# NinjaLAMP_Arduino_simple.net
KiCad netlist of a schematic drawn in EAGLE
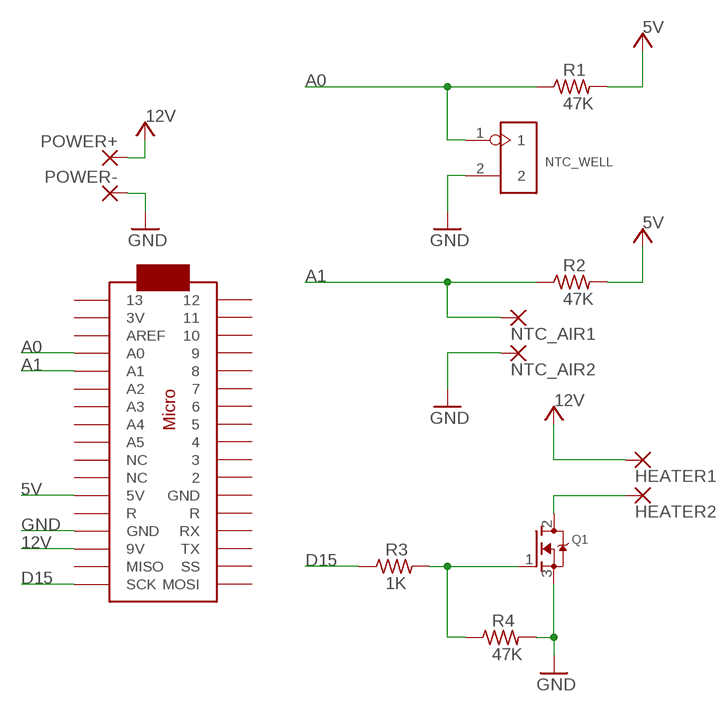
[diagram p0: schematic, sheet 1]

(export (version "E")
  (design (tool "Eeschema 10.0.6"))
  (components
    (comp (ref "HEATER1")
      (value "1,6/0,8")
      (footprint "eagle-import:1,6_0,8")
      (libsource (lib "eagle-import") (part "1,6/0,8"))
    )
    (comp (ref "HEATER2")
      (value "1,6/0,8")
      (footprint "eagle-import:1,6_0,8")
      (libsource (lib "eagle-import") (part "1,6/0,8"))
    )
    (comp (ref "NTC_AIR1")
      (value "1,6/0,8")
      (footprint "eagle-import:1,6_0,8")
      (libsource (lib "eagle-import") (part "1,6/0,8"))
    )
    (comp (ref "NTC_AIR2")
      (value "1,6/0,8")
      (footprint "eagle-import:1,6_0,8")
      (libsource (lib "eagle-import") (part "1,6/0,8"))
    )
    (comp (ref "NTC_WELL")
      (value "2p-2.54")
      (footprint "eagle-import:H2-2.54")
      (fields (field (name "MPN") "P125-1102A0BS116A1"))
      (libsource (lib "eagle-import") (part "DIP-BLACK-MALE-HEADER-VERT(2P-2.54)"))
    )
    (comp (ref "POWER+")
      (value "1,6/0,8")
      (footprint "eagle-import:1,6_0,8")
      (libsource (lib "eagle-import") (part "1,6/0,8"))
    )
    (comp (ref "POWER-")
      (value "1,6/0,8")
      (footprint "eagle-import:1,6_0,8")
      (libsource (lib "eagle-import") (part "1,6/0,8"))
    )
    (comp (ref "Q1")
      (value "MOSFET-NGDS_TO220V")
      (footprint "eagle-import:TO220V")
      (libsource (lib "eagle-import") (part "MOSFET-NGDS_TO220V"))
    )
    (comp (ref "R1")
      (value "47K")
      (footprint "eagle-import:0207_10")
      (libsource (lib "eagle-import") (part "R-US_0207/10"))
    )
    (comp (ref "R2")
      (value "47K")
      (footprint "eagle-import:0207_10")
      (libsource (lib "eagle-import") (part "R-US_0207/10"))
    )
    (comp (ref "R3")
      (value "1K")
      (footprint "eagle-import:0207_10")
      (libsource (lib "eagle-import") (part "R-US_0207/10"))
    )
    (comp (ref "R4")
      (value "47K")
      (footprint "eagle-import:0207_10")
      (libsource (lib "eagle-import") (part "R-US_0207/10"))
    )
    (comp (ref "U$1")
      (value "ARDUINOMICRO")
      (footprint "eagle-import:ARDUINOMICRO")
      (libsource (lib "eagle-import") (part "ARDUINOMICRO"))
    )
  )
  (nets
    (net (code "1") (name "/A0") (class "Default")
      (node (ref "NTC_WELL") (pin "1") (pinfunction "1_1") (pintype "bidirectional"))
      (node (ref "R1") (pin "1") (pinfunction "1_1") (pintype "passive"))
      (node (ref "U$1") (pin "P$31") (pinfunction "A0_P$31") (pintype "bidirectional"))
    )
    (net (code "2") (name "/A1") (class "Default")
      (node (ref "NTC_AIR1") (pin "1") (pinfunction "P_1") (pintype "passive"))
      (node (ref "R2") (pin "1") (pinfunction "1_1") (pintype "passive"))
      (node (ref "U$1") (pin "P$30") (pinfunction "A1_P$30") (pintype "bidirectional"))
    )
    (net (code "3") (name "/D15") (class "Default")
      (node (ref "R3") (pin "1") (pinfunction "1_1") (pintype "passive"))
      (node (ref "U$1") (pin "P$18") (pinfunction "SCK_P$18") (pintype "bidirectional"))
    )
    (net (code "4") (name "5V") (class "Default")
      (node (ref "R1") (pin "2") (pinfunction "2_2") (pintype "passive"))
      (node (ref "R2") (pin "2") (pinfunction "2_2") (pintype "passive"))
      (node (ref "U$1") (pin "P$23") (pinfunction "5V_P$23") (pintype "bidirectional"))
    )
    (net (code "5") (name "12V") (class "Default")
      (node (ref "HEATER1") (pin "1") (pinfunction "P_1") (pintype "passive"))
      (node (ref "POWER+") (pin "1") (pinfunction "P_1") (pintype "passive"))
      (node (ref "U$1") (pin "P$20") (pinfunction "9V_P$20") (pintype "bidirectional"))
    )
    (net (code "6") (name "GND") (class "Default")
      (node (ref "NTC_AIR2") (pin "1") (pinfunction "P_1") (pintype "passive"))
      (node (ref "NTC_WELL") (pin "2") (pinfunction "2_2") (pintype "bidirectional"))
      (node (ref "POWER-") (pin "1") (pinfunction "P_1") (pintype "passive"))
      (node (ref "Q1") (pin "3") (pinfunction "S_3") (pintype "bidirectional"))
      (node (ref "R4") (pin "2") (pinfunction "2_2") (pintype "passive"))
      (node (ref "U$1") (pin "P$12") (pinfunction "GND_P$12") (pintype "bidirectional"))
    )
    (net (code "7") (name "Net-(HEATER2-P)") (class "Default")
      (node (ref "HEATER2") (pin "1") (pinfunction "P_1") (pintype "passive"))
      (node (ref "Q1") (pin "2") (pinfunction "D_2") (pintype "bidirectional"))
    )
    (net (code "8") (name "Net-(Q1-G)") (class "Default")
      (node (ref "Q1") (pin "1") (pinfunction "G_1") (pintype "bidirectional"))
      (node (ref "R3") (pin "2") (pinfunction "2_2") (pintype "passive"))
      (node (ref "R4") (pin "1") (pinfunction "1_1") (pintype "passive"))
    )
    (net (code "9") (name "unconnected-(U$1-2-PadP$11)") (class "Default")
      (node (ref "U$1") (pin "P$11") (pinfunction "2_P$11") (pintype "bidirectional"))
    )
    (net (code "10") (name "unconnected-(U$1-3-PadP$10)") (class "Default")
      (node (ref "U$1") (pin "P$10") (pinfunction "3_P$10") (pintype "bidirectional"))
    )
    (net (code "11") (name "unconnected-(U$1-3V-PadP$33)") (class "Default")
      (node (ref "U$1") (pin "P$33") (pinfunction "3V_P$33") (pintype "bidirectional"))
    )
    (net (code "12") (name "unconnected-(U$1-4-PadP$9)") (class "Default")
      (node (ref "U$1") (pin "P$9") (pinfunction "4_P$9") (pintype "bidirectional"))
    )
    (net (code "13") (name "unconnected-(U$1-5-PadP$8)") (class "Default")
      (node (ref "U$1") (pin "P$8") (pinfunction "5_P$8") (pintype "bidirectional"))
    )
    (net (code "14") (name "unconnected-(U$1-6-PadP$7)") (class "Default")
      (node (ref "U$1") (pin "P$7") (pinfunction "6_P$7") (pintype "bidirectional"))
    )
    (net (code "15") (name "unconnected-(U$1-7-PadP$6)") (class "Default")
      (node (ref "U$1") (pin "P$6") (pinfunction "7_P$6") (pintype "bidirectional"))
    )
    (net (code "16") (name "unconnected-(U$1-8-PadP$5)") (class "Default")
      (node (ref "U$1") (pin "P$5") (pinfunction "8_P$5") (pintype "bidirectional"))
    )
    (net (code "17") (name "unconnected-(U$1-9-PadP$4)") (class "Default")
      (node (ref "U$1") (pin "P$4") (pinfunction "9_P$4") (pintype "bidirectional"))
    )
    (net (code "18") (name "unconnected-(U$1-10-PadP$3)") (class "Default")
      (node (ref "U$1") (pin "P$3") (pinfunction "10_P$3") (pintype "bidirectional"))
    )
    (net (code "19") (name "unconnected-(U$1-11-PadP$2)") (class "Default")
      (node (ref "U$1") (pin "P$2") (pinfunction "11_P$2") (pintype "bidirectional"))
    )
    (net (code "20") (name "unconnected-(U$1-12-PadP$1)") (class "Default")
      (node (ref "U$1") (pin "P$1") (pinfunction "12_P$1") (pintype "bidirectional"))
    )
    (net (code "21") (name "unconnected-(U$1-13-PadP$34)") (class "Default")
      (node (ref "U$1") (pin "P$34") (pinfunction "13_P$34") (pintype "bidirectional"))
    )
    (net (code "22") (name "unconnected-(U$1-A2-PadP$29)") (class "Default")
      (node (ref "U$1") (pin "P$29") (pinfunction "A2_P$29") (pintype "bidirectional"))
    )
    (net (code "23") (name "unconnected-(U$1-A3-PadP$28)") (class "Default")
      (node (ref "U$1") (pin "P$28") (pinfunction "A3_P$28") (pintype "bidirectional"))
    )
    (net (code "24") (name "unconnected-(U$1-A4-PadP$27)") (class "Default")
      (node (ref "U$1") (pin "P$27") (pinfunction "A4_P$27") (pintype "bidirectional"))
    )
    (net (code "25") (name "unconnected-(U$1-A5-PadP$26)") (class "Default")
      (node (ref "U$1") (pin "P$26") (pinfunction "A5_P$26") (pintype "bidirectional"))
    )
    (net (code "26") (name "unconnected-(U$1-AREF-PadP$32)") (class "Default")
      (node (ref "U$1") (pin "P$32") (pinfunction "AREF_P$32") (pintype "bidirectional"))
    )
    (net (code "27") (name "unconnected-(U$1-GND-PadP$21)") (class "Default")
      (node (ref "U$1") (pin "P$21") (pinfunction "GND_P$21") (pintype "bidirectional"))
    )
    (net (code "28") (name "unconnected-(U$1-MISO-PadP$19)") (class "Default")
      (node (ref "U$1") (pin "P$19") (pinfunction "MISO_P$19") (pintype "bidirectional"))
    )
    (net (code "29") (name "unconnected-(U$1-MOSI-PadP$17)") (class "Default")
      (node (ref "U$1") (pin "P$17") (pinfunction "MOSI_P$17") (pintype "bidirectional"))
    )
    (net (code "30") (name "unconnected-(U$1-NC-PadP$24)") (class "Default")
      (node (ref "U$1") (pin "P$24") (pinfunction "NC_P$24") (pintype "bidirectional"))
    )
    (net (code "31") (name "unconnected-(U$1-NC-PadP$25)") (class "Default")
      (node (ref "U$1") (pin "P$25") (pinfunction "NC_P$25") (pintype "bidirectional"))
    )
    (net (code "32") (name "unconnected-(U$1-R-PadP$13)") (class "Default")
      (node (ref "U$1") (pin "P$13") (pinfunction "R_P$13") (pintype "bidirectional"))
    )
    (net (code "33") (name "unconnected-(U$1-R-PadP$22)") (class "Default")
      (node (ref "U$1") (pin "P$22") (pinfunction "R_P$22") (pintype "bidirectional"))
    )
    (net (code "34") (name "unconnected-(U$1-RX-PadP$14)") (class "Default")
      (node (ref "U$1") (pin "P$14") (pinfunction "RX_P$14") (pintype "bidirectional"))
    )
    (net (code "35") (name "unconnected-(U$1-SS-PadP$16)") (class "Default")
      (node (ref "U$1") (pin "P$16") (pinfunction "SS_P$16") (pintype "bidirectional"))
    )
    (net (code "36") (name "unconnected-(U$1-TX-PadP$15)") (class "Default")
      (node (ref "U$1") (pin "P$15") (pinfunction "TX_P$15") (pintype "bidirectional"))
    )
  )
)
